# lower-board.net
KiCad netlist of a schematic drawn in EAGLE
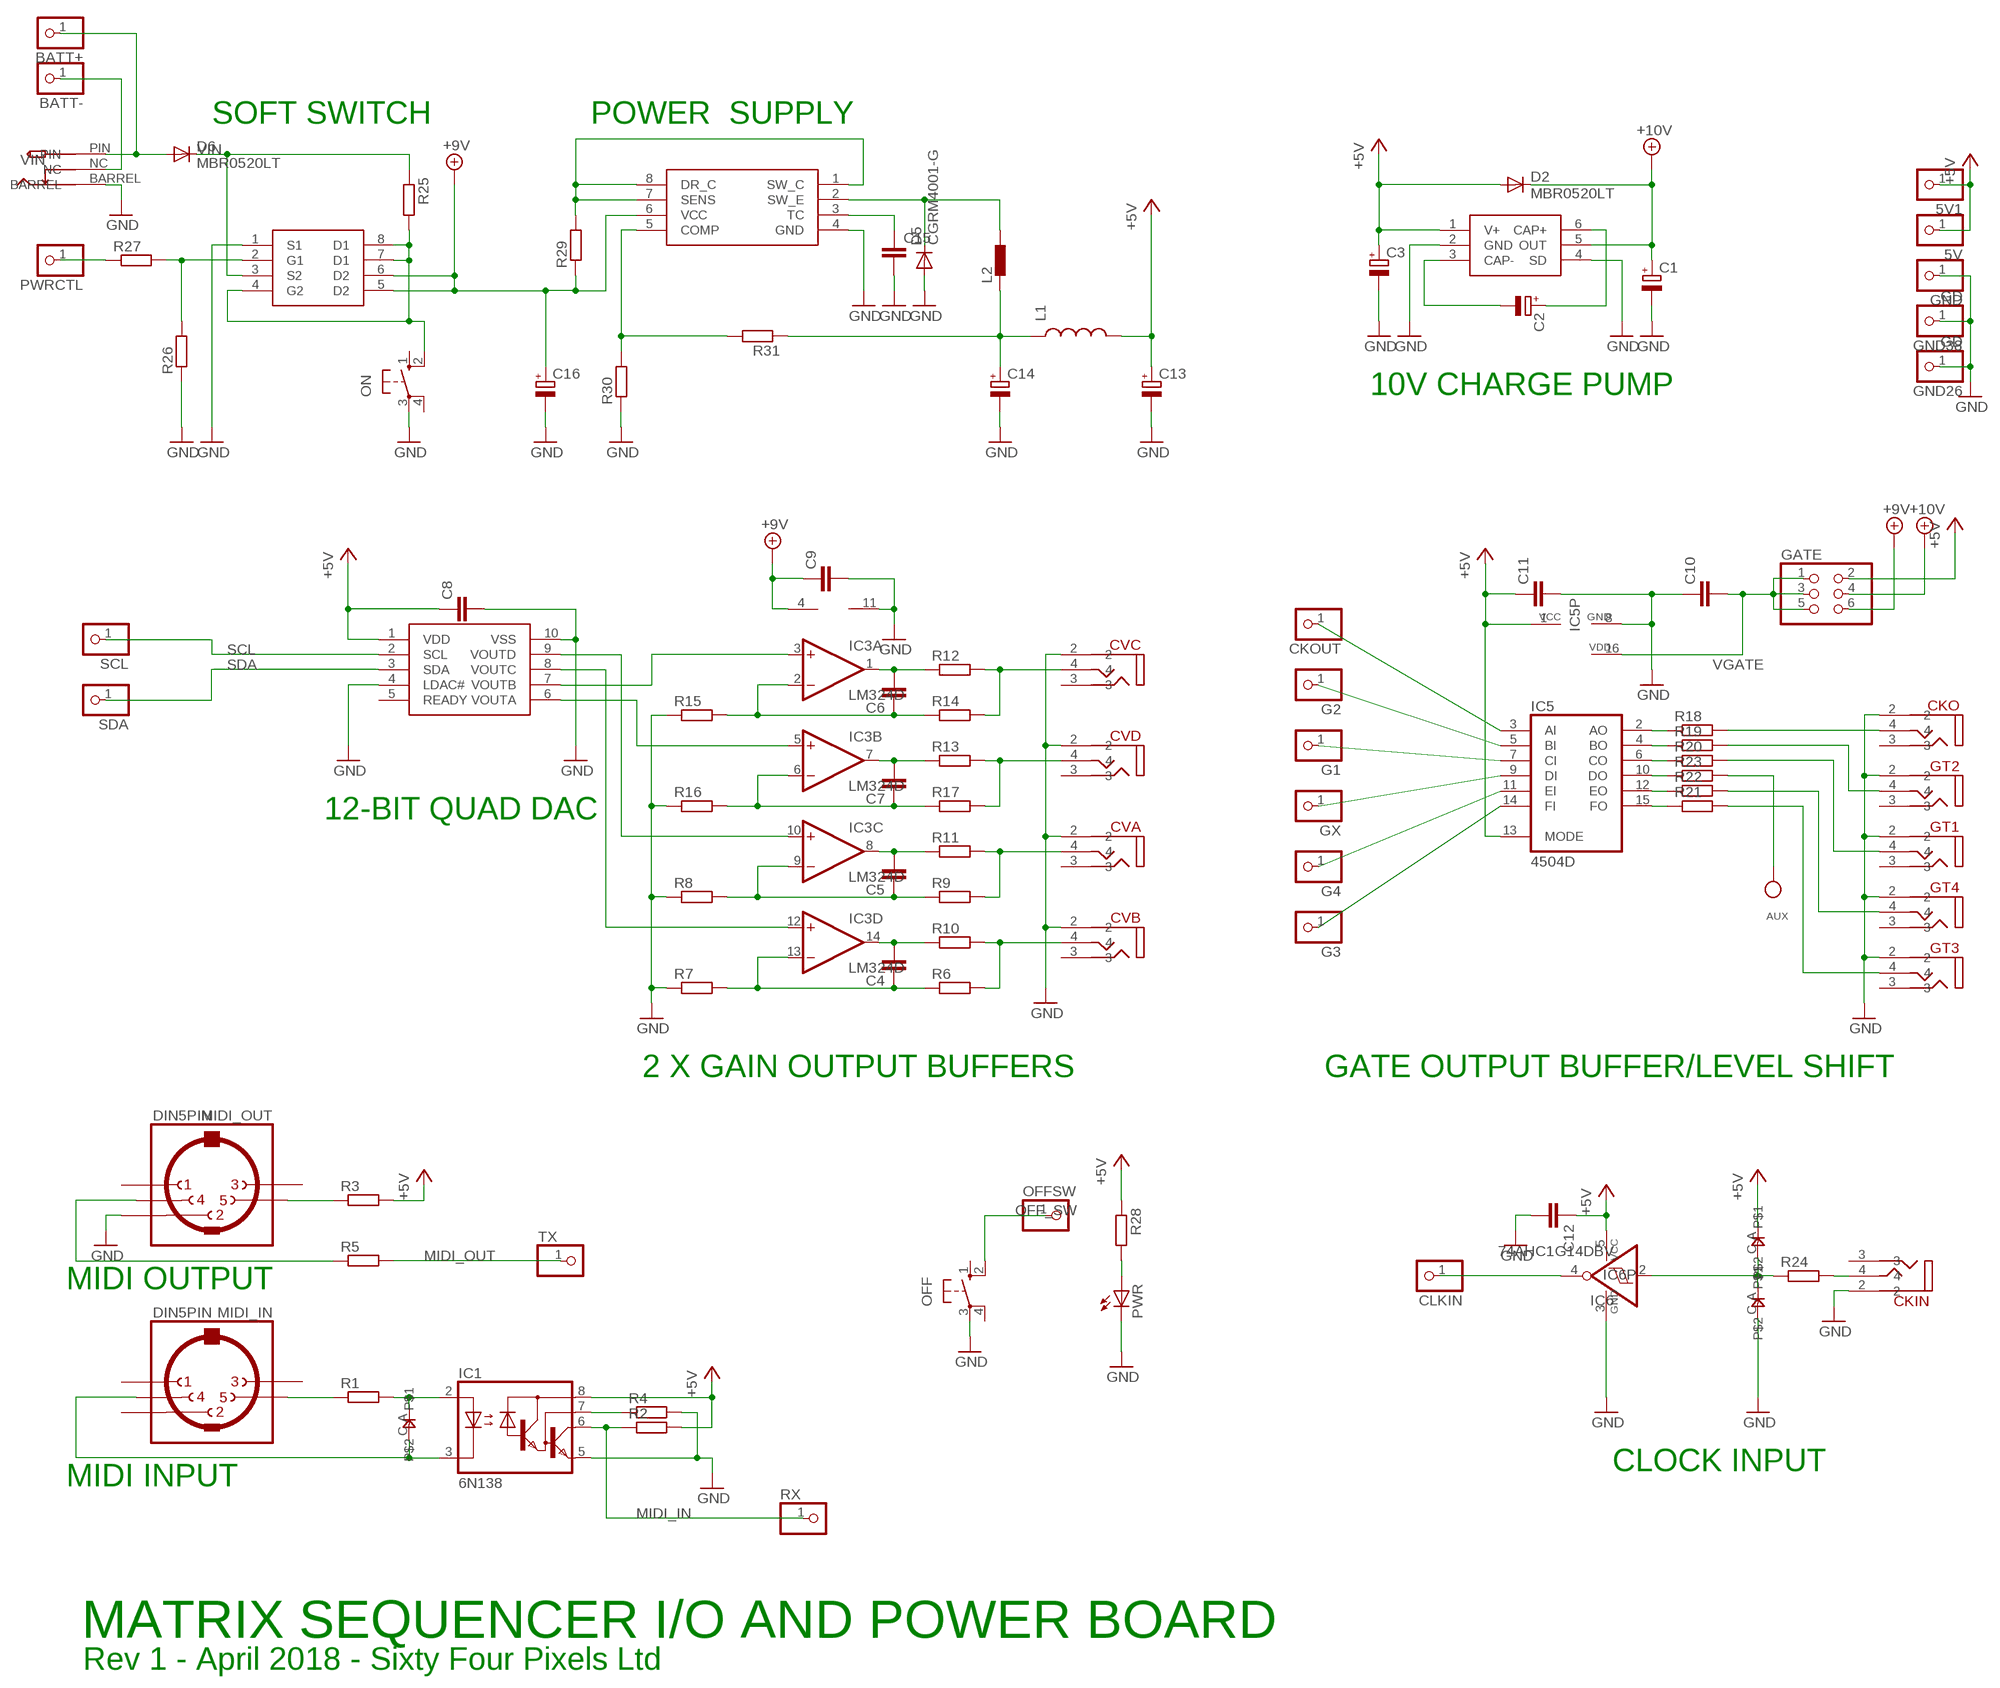
[diagram p0: schematic, sheet 1]

(export (version "E")
  (design (tool "Eeschema 10.0.6"))
  (components
    (comp (ref "5V")
      (value "PINHD-1X1")
      (footprint "eagle-import:1X01")
      (libsource (lib "eagle-import") (part "PINHD-1X1"))
    )
    (comp (ref "5V1")
      (value "PINHD-1X1")
      (footprint "eagle-import:1X01")
      (libsource (lib "eagle-import") (part "PINHD-1X1"))
    )
    (comp (ref "AUX")
      (value "TESTPOINTROUND2MM")
      (footprint "eagle-import:TESTPOINT_ROUND_2MM")
      (libsource (lib "eagle-import") (part "TESTPOINTROUND2MM"))
    )
    (comp (ref "BATT+")
      (value "PINHD-1X1")
      (footprint "eagle-import:1X01")
      (libsource (lib "eagle-import") (part "PINHD-1X1"))
    )
    (comp (ref "BATT-")
      (value "PINHD-1X1")
      (footprint "eagle-import:1X01")
      (libsource (lib "eagle-import") (part "PINHD-1X1"))
    )
    (comp (ref "C1")
      (value "CPOL-EUSMCA")
      (footprint "eagle-import:SMC_A")
      (libsource (lib "eagle-import") (part "CPOL-EUSMCA"))
    )
    (comp (ref "C2")
      (value "CPOL-EUSMCA")
      (footprint "eagle-import:SMC_A")
      (libsource (lib "eagle-import") (part "CPOL-EUSMCA"))
    )
    (comp (ref "C3")
      (value "CPOL-EUSMCA")
      (footprint "eagle-import:SMC_A")
      (libsource (lib "eagle-import") (part "CPOL-EUSMCA"))
    )
    (comp (ref "C4")
      (value "C-EUC0805")
      (footprint "eagle-import:C0805")
      (libsource (lib "eagle-import") (part "C-EUC0805"))
    )
    (comp (ref "C5")
      (value "C-EUC0805")
      (footprint "eagle-import:C0805")
      (libsource (lib "eagle-import") (part "C-EUC0805"))
    )
    (comp (ref "C6")
      (value "C-EUC0805")
      (footprint "eagle-import:C0805")
      (libsource (lib "eagle-import") (part "C-EUC0805"))
    )
    (comp (ref "C7")
      (value "C-EUC0805")
      (footprint "eagle-import:C0805")
      (libsource (lib "eagle-import") (part "C-EUC0805"))
    )
    (comp (ref "C8")
      (value "C-EUC0805")
      (footprint "eagle-import:C0805")
      (libsource (lib "eagle-import") (part "C-EUC0805"))
    )
    (comp (ref "C9")
      (value "C-EUC0805")
      (footprint "eagle-import:C0805")
      (libsource (lib "eagle-import") (part "C-EUC0805"))
    )
    (comp (ref "C10")
      (value "C-EUC0805")
      (footprint "eagle-import:C0805")
      (libsource (lib "eagle-import") (part "C-EUC0805"))
    )
    (comp (ref "C11")
      (value "C-EUC0805")
      (footprint "eagle-import:C0805")
      (libsource (lib "eagle-import") (part "C-EUC0805"))
    )
    (comp (ref "C12")
      (value "C-EUC0805")
      (footprint "eagle-import:C0805")
      (libsource (lib "eagle-import") (part "C-EUC0805"))
    )
    (comp (ref "C13")
      (value "CPOL-EUE2.5-7")
      (footprint "eagle-import:E2,5-7")
      (libsource (lib "eagle-import") (part "CPOL-EUE2.5-7"))
    )
    (comp (ref "C14")
      (value "CPOL-EUE2.5-7")
      (footprint "eagle-import:E2,5-7")
      (libsource (lib "eagle-import") (part "CPOL-EUE2.5-7"))
    )
    (comp (ref "C15")
      (value "C-EUC0805")
      (footprint "eagle-import:C0805")
      (libsource (lib "eagle-import") (part "C-EUC0805"))
    )
    (comp (ref "C16")
      (value "CPOL-EUE2.5-7")
      (footprint "eagle-import:E2,5-7")
      (libsource (lib "eagle-import") (part "CPOL-EUE2.5-7"))
    )
    (comp (ref "CKIN")
      (value "VERTICAL_3_5MM_SOCKET")
      (footprint "eagle-import:VERTICAL_3_5MM_SOCKET")
      (libsource (lib "eagle-import") (part "VERTICAL_3_5MM_SOCKET"))
    )
    (comp (ref "CKO")
      (value "VERTICAL_3_5MM_SOCKET")
      (footprint "eagle-import:VERTICAL_3_5MM_SOCKET")
      (libsource (lib "eagle-import") (part "VERTICAL_3_5MM_SOCKET"))
    )
    (comp (ref "CKOUT")
      (value "PINHD-1X1")
      (footprint "eagle-import:1X01")
      (libsource (lib "eagle-import") (part "PINHD-1X1"))
    )
    (comp (ref "CLKIN")
      (value "PINHD-1X1")
      (footprint "eagle-import:1X01")
      (libsource (lib "eagle-import") (part "PINHD-1X1"))
    )
    (comp (ref "CVA")
      (value "VERTICAL_3_5MM_SOCKET")
      (footprint "eagle-import:VERTICAL_3_5MM_SOCKET")
      (libsource (lib "eagle-import") (part "VERTICAL_3_5MM_SOCKET"))
    )
    (comp (ref "CVB")
      (value "VERTICAL_3_5MM_SOCKET")
      (footprint "eagle-import:VERTICAL_3_5MM_SOCKET")
      (libsource (lib "eagle-import") (part "VERTICAL_3_5MM_SOCKET"))
    )
    (comp (ref "CVC")
      (value "VERTICAL_3_5MM_SOCKET")
      (footprint "eagle-import:VERTICAL_3_5MM_SOCKET")
      (libsource (lib "eagle-import") (part "VERTICAL_3_5MM_SOCKET"))
    )
    (comp (ref "CVD")
      (value "VERTICAL_3_5MM_SOCKET")
      (footprint "eagle-import:VERTICAL_3_5MM_SOCKET")
      (libsource (lib "eagle-import") (part "VERTICAL_3_5MM_SOCKET"))
    )
    (comp (ref "D1")
      (value "0805DIODE")
      (footprint "eagle-import:0805DIODE")
      (libsource (lib "eagle-import") (part "0805DIODE"))
    )
    (comp (ref "D2")
      (value "MBR0520LT")
      (footprint "eagle-import:SOD123")
      (libsource (lib "eagle-import") (part "MBR0520LT"))
    )
    (comp (ref "D3")
      (value "0805DIODE")
      (footprint "eagle-import:0805DIODE")
      (libsource (lib "eagle-import") (part "0805DIODE"))
    )
    (comp (ref "D4")
      (value "0805DIODE")
      (footprint "eagle-import:0805DIODE")
      (libsource (lib "eagle-import") (part "0805DIODE"))
    )
    (comp (ref "D5")
      (value "CGRM4001-G")
      (footprint "eagle-import:SOD-123_MINI-SMA")
      (libsource (lib "eagle-import") (part "CGRM400-G1"))
    )
    (comp (ref "D6")
      (value "MBR0520LT")
      (footprint "eagle-import:SOD123")
      (libsource (lib "eagle-import") (part "MBR0520LT"))
    )
    (comp (ref "G1")
      (value "PINHD-1X1")
      (footprint "eagle-import:1X01")
      (libsource (lib "eagle-import") (part "PINHD-1X1"))
    )
    (comp (ref "G2")
      (value "PINHD-1X1")
      (footprint "eagle-import:1X01")
      (libsource (lib "eagle-import") (part "PINHD-1X1"))
    )
    (comp (ref "G3")
      (value "PINHD-1X1")
      (footprint "eagle-import:1X01")
      (libsource (lib "eagle-import") (part "PINHD-1X1"))
    )
    (comp (ref "G4")
      (value "PINHD-1X1")
      (footprint "eagle-import:1X01")
      (libsource (lib "eagle-import") (part "PINHD-1X1"))
    )
    (comp (ref "GATE")
      (value "PINHD-2X3")
      (footprint "eagle-import:2X03")
      (libsource (lib "eagle-import") (part "PINHD-2X3"))
    )
    (comp (ref "GND")
      (value "PINHD-1X1")
      (footprint "eagle-import:1X01")
      (libsource (lib "eagle-import") (part "PINHD-1X1"))
    )
    (comp (ref "GND26")
      (value "GD")
      (footprint "eagle-import:1X01")
      (libsource (lib "eagle-import") (part "PINHD-1X1"))
    )
    (comp (ref "GND38")
      (value "GD")
      (footprint "eagle-import:1X01")
      (libsource (lib "eagle-import") (part "PINHD-1X1"))
    )
    (comp (ref "GT1")
      (value "VERTICAL_3_5MM_SOCKET")
      (footprint "eagle-import:VERTICAL_3_5MM_SOCKET")
      (libsource (lib "eagle-import") (part "VERTICAL_3_5MM_SOCKET"))
    )
    (comp (ref "GT2")
      (value "VERTICAL_3_5MM_SOCKET")
      (footprint "eagle-import:VERTICAL_3_5MM_SOCKET")
      (libsource (lib "eagle-import") (part "VERTICAL_3_5MM_SOCKET"))
    )
    (comp (ref "GT3")
      (value "VERTICAL_3_5MM_SOCKET")
      (footprint "eagle-import:VERTICAL_3_5MM_SOCKET")
      (libsource (lib "eagle-import") (part "VERTICAL_3_5MM_SOCKET"))
    )
    (comp (ref "GT4")
      (value "VERTICAL_3_5MM_SOCKET")
      (footprint "eagle-import:VERTICAL_3_5MM_SOCKET")
      (libsource (lib "eagle-import") (part "VERTICAL_3_5MM_SOCKET"))
    )
    (comp (ref "GX")
      (value "PINHD-1X1")
      (footprint "eagle-import:1X01")
      (libsource (lib "eagle-import") (part "PINHD-1X1"))
    )
    (comp (ref "IC1")
      (value "6N138")
      (footprint "eagle-import:DIL08")
      (fields (field (name "MF") "VISHAY/TELEFUNKEN"))
      (libsource (lib "eagle-import") (part "6N138"))
    )
    (comp (ref "IC2")
      (value "LM27675M5_CHARGEPUMP")
      (footprint "eagle-import:SOT23-6")
      (libsource (lib "eagle-import") (part "LM27675M5_CHARGEPUMP"))
    )
    (comp (ref "IC3")
      (value "LM324D")
      (footprint "eagle-import:SO14")
      (libsource (lib "eagle-import") (part "LM324D"))
    )
    (comp (ref "IC4")
      (value "MCP4728_QUAD_DAC")
      (footprint "eagle-import:MSOP10")
      (libsource (lib "eagle-import") (part "MCP4728_QUAD_DAC"))
    )
    (comp (ref "IC5")
      (value "4504D")
      (footprint "eagle-import:SO16")
      (libsource (lib "eagle-import") (part "4504D"))
    )
    (comp (ref "IC6")
      (value "74AHC1G14DBV")
      (footprint "eagle-import:SOT23-5")
      (libsource (lib "eagle-import") (part "741G14DBVAHC"))
    )
    (comp (ref "IC7")
      (value "FDS8958B")
      (footprint "eagle-import:SOIC8")
      (libsource (lib "eagle-import") (part "FDS8958B"))
    )
    (comp (ref "IC8")
      (value "SP34063A_BOOST_REG")
      (footprint "eagle-import:SOIC8")
      (libsource (lib "eagle-import") (part "SP34063A_BOOST_REG"))
    )
    (comp (ref "L1")
      (value "INDUCTOR1210")
      (footprint "eagle-import:1210")
      (libsource (lib "eagle-import") (part "INDUCTOR1210"))
    )
    (comp (ref "L2")
      (value "DR1030")
      (footprint "eagle-import:DR1030")
      (libsource (lib "eagle-import") (part "DR1030"))
    )
    (comp (ref "MIDI_IN")
      (value "DIN5PIN")
      (footprint "eagle-import:EDGEDIN")
      (libsource (lib "eagle-import") (part "DIN5PIN"))
    )
    (comp (ref "MIDI_OUT")
      (value "DIN5PIN")
      (footprint "eagle-import:EDGEDIN")
      (libsource (lib "eagle-import") (part "DIN5PIN"))
    )
    (comp (ref "OFF")
      (value "10-XX")
      (footprint "eagle-import:B3F-10XX")
      (fields (field (name "MPN") "B3F-1000"))
      (libsource (lib "eagle-import") (part "10-XX"))
    )
    (comp (ref "OFFSW")
      (value "PINHD-1X1")
      (footprint "eagle-import:1X01")
      (libsource (lib "eagle-import") (part "PINHD-1X1"))
    )
    (comp (ref "ON")
      (value "10-XX")
      (footprint "eagle-import:B3F-10XX")
      (fields (field (name "MPN") "B3F-1000"))
      (libsource (lib "eagle-import") (part "10-XX"))
    )
    (comp (ref "PWR")
      (value "LED3MM")
      (footprint "eagle-import:LED3MM")
      (libsource (lib "eagle-import") (part "LED3MM"))
    )
    (comp (ref "PWRCTL")
      (value "PINHD-1X1")
      (footprint "eagle-import:1X01")
      (libsource (lib "eagle-import") (part "PINHD-1X1"))
    )
    (comp (ref "R1")
      (value "R-EU_R0805")
      (footprint "eagle-import:R0805")
      (libsource (lib "eagle-import") (part "R-EU_R0805"))
    )
    (comp (ref "R2")
      (value "R-EU_R0805")
      (footprint "eagle-import:R0805")
      (libsource (lib "eagle-import") (part "R-EU_R0805"))
    )
    (comp (ref "R3")
      (value "R-EU_R0805")
      (footprint "eagle-import:R0805")
      (libsource (lib "eagle-import") (part "R-EU_R0805"))
    )
    (comp (ref "R4")
      (value "R-EU_R0805")
      (footprint "eagle-import:R0805")
      (libsource (lib "eagle-import") (part "R-EU_R0805"))
    )
    (comp (ref "R5")
      (value "R-EU_R0805")
      (footprint "eagle-import:R0805")
      (libsource (lib "eagle-import") (part "R-EU_R0805"))
    )
    (comp (ref "R6")
      (value "R-EU_R0805")
      (footprint "eagle-import:R0805")
      (libsource (lib "eagle-import") (part "R-EU_R0805"))
    )
    (comp (ref "R7")
      (value "R-EU_R0805")
      (footprint "eagle-import:R0805")
      (libsource (lib "eagle-import") (part "R-EU_R0805"))
    )
    (comp (ref "R8")
      (value "R-EU_R0805")
      (footprint "eagle-import:R0805")
      (libsource (lib "eagle-import") (part "R-EU_R0805"))
    )
    (comp (ref "R9")
      (value "R-EU_R0805")
      (footprint "eagle-import:R0805")
      (libsource (lib "eagle-import") (part "R-EU_R0805"))
    )
    (comp (ref "R10")
      (value "R-EU_R0805")
      (footprint "eagle-import:R0805")
      (libsource (lib "eagle-import") (part "R-EU_R0805"))
    )
    (comp (ref "R11")
      (value "R-EU_R0805")
      (footprint "eagle-import:R0805")
      (libsource (lib "eagle-import") (part "R-EU_R0805"))
    )
    (comp (ref "R12")
      (value "R-EU_R0805")
      (footprint "eagle-import:R0805")
      (libsource (lib "eagle-import") (part "R-EU_R0805"))
    )
    (comp (ref "R13")
      (value "R-EU_R0805")
      (footprint "eagle-import:R0805")
      (libsource (lib "eagle-import") (part "R-EU_R0805"))
    )
    (comp (ref "R14")
      (value "R-EU_R0805")
      (footprint "eagle-import:R0805")
      (libsource (lib "eagle-import") (part "R-EU_R0805"))
    )
    (comp (ref "R15")
      (value "R-EU_R0805")
      (footprint "eagle-import:R0805")
      (libsource (lib "eagle-import") (part "R-EU_R0805"))
    )
    (comp (ref "R16")
      (value "R-EU_R0805")
      (footprint "eagle-import:R0805")
      (libsource (lib "eagle-import") (part "R-EU_R0805"))
    )
    (comp (ref "R17")
      (value "R-EU_R0805")
      (footprint "eagle-import:R0805")
      (libsource (lib "eagle-import") (part "R-EU_R0805"))
    )
    (comp (ref "R18")
      (value "R-EU_R0805")
      (footprint "eagle-import:R0805")
      (libsource (lib "eagle-import") (part "R-EU_R0805"))
    )
    (comp (ref "R19")
      (value "R-EU_R0805")
      (footprint "eagle-import:R0805")
      (libsource (lib "eagle-import") (part "R-EU_R0805"))
    )
    (comp (ref "R20")
      (value "R-EU_R0805")
      (footprint "eagle-import:R0805")
      (libsource (lib "eagle-import") (part "R-EU_R0805"))
    )
    (comp (ref "R21")
      (value "R-EU_R0805")
      (footprint "eagle-import:R0805")
      (libsource (lib "eagle-import") (part "R-EU_R0805"))
    )
    (comp (ref "R22")
      (value "R-EU_R0805")
      (footprint "eagle-import:R0805")
      (libsource (lib "eagle-import") (part "R-EU_R0805"))
    )
    (comp (ref "R23")
      (value "R-EU_R0805")
      (footprint "eagle-import:R0805")
      (libsource (lib "eagle-import") (part "R-EU_R0805"))
    )
    (comp (ref "R24")
      (value "R-EU_R0805")
      (footprint "eagle-import:R0805")
      (libsource (lib "eagle-import") (part "R-EU_R0805"))
    )
    (comp (ref "R25")
      (value "R-EU_R0805")
      (footprint "eagle-import:R0805")
      (libsource (lib "eagle-import") (part "R-EU_R0805"))
    )
    (comp (ref "R26")
      (value "R-EU_R0805")
      (footprint "eagle-import:R0805")
      (libsource (lib "eagle-import") (part "R-EU_R0805"))
    )
    (comp (ref "R27")
      (value "R-EU_R0805")
      (footprint "eagle-import:R0805")
      (libsource (lib "eagle-import") (part "R-EU_R0805"))
    )
    (comp (ref "R28")
      (value "R-EU_R0805")
      (footprint "eagle-import:R0805")
      (libsource (lib "eagle-import") (part "R-EU_R0805"))
    )
    (comp (ref "R29")
      (value "R-EU_R0805")
      (footprint "eagle-import:R0805")
      (libsource (lib "eagle-import") (part "R-EU_R0805"))
    )
    (comp (ref "R30")
      (value "R-EU_R0805")
      (footprint "eagle-import:R0805")
      (libsource (lib "eagle-import") (part "R-EU_R0805"))
    )
    (comp (ref "R31")
      (value "R-EU_R0805")
      (footprint "eagle-import:R0805")
      (libsource (lib "eagle-import") (part "R-EU_R0805"))
    )
    (comp (ref "RX")
      (value "PINHD-1X1")
      (footprint "eagle-import:1X01")
      (libsource (lib "eagle-import") (part "PINHD-1X1"))
    )
    (comp (ref "SCL")
      (value "PINHD-1X1")
      (footprint "eagle-import:1X01")
      (libsource (lib "eagle-import") (part "PINHD-1X1"))
    )
    (comp (ref "SDA")
      (value "PINHD-1X1")
      (footprint "eagle-import:1X01")
      (libsource (lib "eagle-import") (part "PINHD-1X1"))
    )
    (comp (ref "TX")
      (value "PINHD-1X1")
      (footprint "eagle-import:1X01")
      (libsource (lib "eagle-import") (part "PINHD-1X1"))
    )
    (comp (ref "U$1")
      (value "PWR_SOCKET_2_1MM")
      (footprint "eagle-import:PWR_SOCKET_2_1MM")
      (libsource (lib "eagle-import") (part "PWR_SOCKET_2_1MM"))
    )
  )
  (nets
    (net (code "1") (name "+5V") (class "Default")
      (node (ref "5V") (pin "1") (pinfunction "1_1") (pintype "passive"))
      (node (ref "5V1") (pin "1") (pinfunction "1_1") (pintype "passive"))
      (node (ref "C11") (pin "1") (pinfunction "1_1") (pintype "passive"))
      (node (ref "C12") (pin "1") (pinfunction "1_1") (pintype "passive"))
      (node (ref "C13") (pin "+") (pinfunction "+_+") (pintype "passive"))
      (node (ref "C3") (pin "+") (pinfunction "+_+") (pintype "passive"))
      (node (ref "C8") (pin "1") (pinfunction "1_1") (pintype "passive"))
      (node (ref "D2") (pin "A") (pinfunction "A_A") (pintype "passive"))
      (node (ref "D3") (pin "A") (pinfunction "P$2_A") (pintype "bidirectional"))
      (node (ref "GATE") (pin "2") (pinfunction "2_2") (pintype "passive"))
      (node (ref "IC1") (pin "8") (pinfunction "VCC_8") (pintype "passive"))
      (node (ref "IC2") (pin "1") (pinfunction "V+_1") (pintype "bidirectional"))
      (node (ref "IC4") (pin "1") (pinfunction "VDD_1") (pintype "power_in"))
      (node (ref "IC5") (pin "1") (pinfunction "VCC_1") (pintype "power_in"))
      (node (ref "IC5") (pin "13") (pinfunction "MODE_13") (pintype "input"))
      (node (ref "IC6") (pin "5") (pinfunction "VCC_5") (pintype "power_in"))
      (node (ref "L1") (pin "2") (pinfunction "2_2") (pintype "passive"))
      (node (ref "R2") (pin "2") (pinfunction "2_2") (pintype "passive"))
      (node (ref "R28") (pin "1") (pinfunction "1_1") (pintype "passive"))
      (node (ref "R3") (pin "2") (pinfunction "2_2") (pintype "passive"))
    )
    (net (code "2") (name "+9V") (class "Default")
      (node (ref "C16") (pin "+") (pinfunction "+_+") (pintype "passive"))
      (node (ref "C9") (pin "1") (pinfunction "1_1") (pintype "passive"))
      (node (ref "GATE") (pin "6") (pinfunction "6_6") (pintype "passive"))
      (node (ref "IC3") (pin "4") (pinfunction "V+_4") (pintype "power_in"))
      (node (ref "IC7") (pin "5") (pinfunction "D2_5") (pintype "bidirectional"))
      (node (ref "IC7") (pin "6") (pinfunction "D2_6") (pintype "bidirectional"))
      (node (ref "IC8") (pin "6") (pinfunction "VCC_6") (pintype "bidirectional"))
      (node (ref "R29") (pin "1") (pinfunction "1_1") (pintype "passive"))
    )
    (net (code "3") (name "+10V") (class "Default")
      (node (ref "C1") (pin "+") (pinfunction "+_+") (pintype "passive"))
      (node (ref "D2") (pin "C") (pinfunction "C_C") (pintype "passive"))
      (node (ref "GATE") (pin "4") (pinfunction "4_4") (pintype "passive"))
      (node (ref "IC2") (pin "5") (pinfunction "OUT_5") (pintype "bidirectional"))
    )
    (net (code "4") (name "/MIDI_IN") (class "Default")
      (node (ref "IC1") (pin "6") (pinfunction "VO_6") (pintype "passive"))
      (node (ref "R2") (pin "1") (pinfunction "1_1") (pintype "passive"))
      (node (ref "RX") (pin "1") (pinfunction "1_1") (pintype "passive"))
    )
    (net (code "5") (name "/MIDI_OUT") (class "Default")
      (node (ref "R5") (pin "2") (pinfunction "2_2") (pintype "passive"))
      (node (ref "TX") (pin "1") (pinfunction "1_1") (pintype "passive"))
    )
    (net (code "6") (name "/OFF_SW") (class "Default")
      (node (ref "OFF") (pin "2") (pinfunction "S1_2") (pintype "passive"))
      (node (ref "OFFSW") (pin "1") (pinfunction "1_1") (pintype "passive"))
    )
    (net (code "7") (name "/SCL") (class "Default")
      (node (ref "IC4") (pin "2") (pinfunction "SCL_2") (pintype "bidirectional"))
      (node (ref "SCL") (pin "1") (pinfunction "1_1") (pintype "passive"))
    )
    (net (code "8") (name "/SDA") (class "Default")
      (node (ref "IC4") (pin "3") (pinfunction "SDA_3") (pintype "bidirectional"))
      (node (ref "SDA") (pin "1") (pinfunction "1_1") (pintype "passive"))
    )
    (net (code "9") (name "/VGATE") (class "Default")
      (node (ref "C10") (pin "2") (pinfunction "2_2") (pintype "passive"))
      (node (ref "GATE") (pin "1") (pinfunction "1_1") (pintype "passive"))
      (node (ref "GATE") (pin "3") (pinfunction "3_3") (pintype "passive"))
      (node (ref "GATE") (pin "5") (pinfunction "5_5") (pintype "passive"))
      (node (ref "IC5") (pin "16") (pinfunction "VDD_16") (pintype "power_in"))
    )
    (net (code "10") (name "/VIN") (class "Default")
      (node (ref "D6") (pin "C") (pinfunction "C_C") (pintype "passive"))
      (node (ref "IC7") (pin "3") (pinfunction "S2_3") (pintype "bidirectional"))
      (node (ref "R25") (pin "1") (pinfunction "1_1") (pintype "passive"))
    )
    (net (code "11") (name "GND") (class "Default")
      (node (ref "C1") (pin "-") (pinfunction "-_-") (pintype "passive"))
      (node (ref "C10") (pin "1") (pinfunction "1_1") (pintype "passive"))
      (node (ref "C11") (pin "2") (pinfunction "2_2") (pintype "passive"))
      (node (ref "C12") (pin "2") (pinfunction "2_2") (pintype "passive"))
      (node (ref "C13") (pin "-") (pinfunction "-_-") (pintype "passive"))
      (node (ref "C14") (pin "-") (pinfunction "-_-") (pintype "passive"))
      (node (ref "C15") (pin "2") (pinfunction "2_2") (pintype "passive"))
      (node (ref "C16") (pin "-") (pinfunction "-_-") (pintype "passive"))
      (node (ref "C3") (pin "-") (pinfunction "-_-") (pintype "passive"))
      (node (ref "C8") (pin "2") (pinfunction "2_2") (pintype "passive"))
      (node (ref "C9") (pin "2") (pinfunction "2_2") (pintype "passive"))
      (node (ref "CKIN") (pin "2") (pinfunction "2_2") (pintype "bidirectional"))
      (node (ref "CKO") (pin "2") (pinfunction "2_2") (pintype "bidirectional"))
      (node (ref "CVA") (pin "2") (pinfunction "2_2") (pintype "bidirectional"))
      (node (ref "CVB") (pin "2") (pinfunction "2_2") (pintype "bidirectional"))
      (node (ref "CVC") (pin "2") (pinfunction "2_2") (pintype "bidirectional"))
      (node (ref "CVD") (pin "2") (pinfunction "2_2") (pintype "bidirectional"))
      (node (ref "D4") (pin "C") (pinfunction "P$1_C") (pintype "bidirectional"))
      (node (ref "D5") (pin "A") (pinfunction "A_A") (pintype "passive"))
      (node (ref "GND") (pin "1") (pinfunction "1_1") (pintype "passive"))
      (node (ref "GND26") (pin "1") (pinfunction "1_1") (pintype "passive"))
      (node (ref "GND38") (pin "1") (pinfunction "1_1") (pintype "passive"))
      (node (ref "GT1") (pin "2") (pinfunction "2_2") (pintype "bidirectional"))
      (node (ref "GT2") (pin "2") (pinfunction "2_2") (pintype "bidirectional"))
      (node (ref "GT3") (pin "2") (pinfunction "2_2") (pintype "bidirectional"))
      (node (ref "GT4") (pin "2") (pinfunction "2_2") (pintype "bidirectional"))
      (node (ref "IC1") (pin "5") (pinfunction "GND_5") (pintype "passive"))
      (node (ref "IC2") (pin "2") (pinfunction "GND_2") (pintype "bidirectional"))
      (node (ref "IC2") (pin "4") (pinfunction "SD_4") (pintype "bidirectional"))
      (node (ref "IC3") (pin "11") (pinfunction "V-_11") (pintype "power_in"))
      (node (ref "IC4") (pin "10") (pinfunction "VSS_10") (pintype "power_in"))
      (node (ref "IC4") (pin "4") (pinfunction "LDAC#_4") (pintype "bidirectional"))
      (node (ref "IC5") (pin "8") (pinfunction "GND_8") (pintype "power_in"))
      (node (ref "IC6") (pin "3") (pinfunction "GND_3") (pintype "power_in"))
      (node (ref "IC7") (pin "1") (pinfunction "S1_1") (pintype "bidirectional"))
      (node (ref "IC8") (pin "4") (pinfunction "GND_4") (pintype "bidirectional"))
      (node (ref "MIDI_OUT") (pin "2") (pinfunction "2_2") (pintype "passive"))
      (node (ref "OFF") (pin "3") (pinfunction "P_3") (pintype "passive"))
      (node (ref "ON") (pin "3") (pinfunction "P_3") (pintype "passive"))
      (node (ref "PWR") (pin "K") (pinfunction "C_K") (pintype "passive"))
      (node (ref "R15") (pin "1") (pinfunction "1_1") (pintype "passive"))
      (node (ref "R16") (pin "1") (pinfunction "1_1") (pintype "passive"))
      (node (ref "R26") (pin "1") (pinfunction "1_1") (pintype "passive"))
      (node (ref "R30") (pin "1") (pinfunction "1_1") (pintype "passive"))
      (node (ref "R4") (pin "2") (pinfunction "2_2") (pintype "passive"))
      (node (ref "R7") (pin "1") (pinfunction "1_1") (pintype "passive"))
      (node (ref "R8") (pin "1") (pinfunction "1_1") (pintype "passive"))
      (node (ref "U$1") (pin "BARREL") (pinfunction "BARREL_BARREL") (pintype "bidirectional"))
    )
    (net (code "12") (name "Net-(AUX-PadP$1)") (class "Default")
      (node (ref "AUX") (pin "P$1") (pinfunction "P$1_P$1") (pintype "bidirectional"))
      (node (ref "R23") (pin "2") (pinfunction "2_2") (pintype "passive"))
    )
    (net (code "13") (name "Net-(BATT+-Pad1)") (class "Default")
      (node (ref "BATT+") (pin "1") (pinfunction "1_1") (pintype "passive"))
      (node (ref "D6") (pin "A") (pinfunction "A_A") (pintype "passive"))
      (node (ref "U$1") (pin "PIN") (pinfunction "PIN_PIN") (pintype "bidirectional"))
    )
    (net (code "14") (name "Net-(BATT--Pad1)") (class "Default")
      (node (ref "BATT-") (pin "1") (pinfunction "1_1") (pintype "passive"))
      (node (ref "U$1") (pin "NC") (pinfunction "NC_NC") (pintype "bidirectional"))
    )
    (net (code "15") (name "Net-(C14-Pad+)") (class "Default")
      (node (ref "C14") (pin "+") (pinfunction "+_+") (pintype "passive"))
      (node (ref "L1") (pin "1") (pinfunction "1_1") (pintype "passive"))
      (node (ref "L2") (pin "1") (pinfunction "1_1") (pintype "passive"))
      (node (ref "R31") (pin "1") (pinfunction "1_1") (pintype "passive"))
    )
    (net (code "16") (name "Net-(CKIN-Pad4)") (class "Default")
      (node (ref "CKIN") (pin "4") (pinfunction "4_4") (pintype "bidirectional"))
      (node (ref "R24") (pin "2") (pinfunction "2_2") (pintype "passive"))
    )
    (net (code "17") (name "Net-(CKO-Pad4)") (class "Default")
      (node (ref "CKO") (pin "4") (pinfunction "4_4") (pintype "bidirectional"))
      (node (ref "R18") (pin "2") (pinfunction "2_2") (pintype "passive"))
    )
    (net (code "18") (name "Net-(CVA-Pad4)") (class "Default")
      (node (ref "CVA") (pin "4") (pinfunction "4_4") (pintype "bidirectional"))
      (node (ref "R11") (pin "2") (pinfunction "2_2") (pintype "passive"))
      (node (ref "R9") (pin "2") (pinfunction "2_2") (pintype "passive"))
    )
    (net (code "19") (name "Net-(CVB-Pad4)") (class "Default")
      (node (ref "CVB") (pin "4") (pinfunction "4_4") (pintype "bidirectional"))
      (node (ref "R10") (pin "2") (pinfunction "2_2") (pintype "passive"))
      (node (ref "R6") (pin "2") (pinfunction "2_2") (pintype "passive"))
    )
    (net (code "20") (name "Net-(CVC-Pad4)") (class "Default")
      (node (ref "CVC") (pin "4") (pinfunction "4_4") (pintype "bidirectional"))
      (node (ref "R12") (pin "2") (pinfunction "2_2") (pintype "passive"))
      (node (ref "R14") (pin "2") (pinfunction "2_2") (pintype "passive"))
    )
    (net (code "21") (name "Net-(CVD-Pad4)") (class "Default")
      (node (ref "CVD") (pin "4") (pinfunction "4_4") (pintype "bidirectional"))
      (node (ref "R13") (pin "2") (pinfunction "2_2") (pintype "passive"))
      (node (ref "R17") (pin "2") (pinfunction "2_2") (pintype "passive"))
    )
    (net (code "22") (name "Net-(D1-P$1)") (class "Default")
      (node (ref "D1") (pin "C") (pinfunction "P$1_C") (pintype "bidirectional"))
      (node (ref "IC1") (pin "3") (pinfunction "C_3") (pintype "passive"))
      (node (ref "MIDI_IN") (pin "4") (pinfunction "4_4") (pintype "passive"))
    )
    (net (code "23") (name "Net-(D1-P$2)") (class "Default")
      (node (ref "D1") (pin "A") (pinfunction "P$2_A") (pintype "bidirectional"))
      (node (ref "IC1") (pin "2") (pinfunction "A_2") (pintype "passive"))
      (node (ref "R1") (pin "2") (pinfunction "2_2") (pintype "passive"))
    )
    (net (code "24") (name "Net-(D3-P$1)") (class "Default")
      (node (ref "D3") (pin "C") (pinfunction "P$1_C") (pintype "bidirectional"))
      (node (ref "D4") (pin "A") (pinfunction "P$2_A") (pintype "bidirectional"))
      (node (ref "IC6") (pin "2") (pinfunction "I_2") (pintype "input"))
      (node (ref "R24") (pin "1") (pinfunction "1_1") (pintype "passive"))
    )
    (net (code "25") (name "Net-(GT1-Pad4)") (class "Default")
      (node (ref "GT1") (pin "4") (pinfunction "4_4") (pintype "bidirectional"))
      (node (ref "R20") (pin "2") (pinfunction "2_2") (pintype "passive"))
    )
    (net (code "26") (name "Net-(GT2-Pad4)") (class "Default")
      (node (ref "GT2") (pin "4") (pinfunction "4_4") (pintype "bidirectional"))
      (node (ref "R19") (pin "2") (pinfunction "2_2") (pintype "passive"))
    )
    (net (code "27") (name "Net-(GT3-Pad4)") (class "Default")
      (node (ref "GT3") (pin "4") (pinfunction "4_4") (pintype "bidirectional"))
      (node (ref "R21") (pin "2") (pinfunction "2_2") (pintype "passive"))
    )
    (net (code "28") (name "Net-(GT4-Pad4)") (class "Default")
      (node (ref "GT4") (pin "4") (pinfunction "4_4") (pintype "bidirectional"))
      (node (ref "R22") (pin "2") (pinfunction "2_2") (pintype "passive"))
    )
    (net (code "29") (name "Net-(IC1-VB)") (class "Default")
      (node (ref "IC1") (pin "7") (pinfunction "VB_7") (pintype "passive"))
      (node (ref "R4") (pin "1") (pinfunction "1_1") (pintype "passive"))
    )
    (net (code "30") (name "Net-(IC2-CAP+)") (class "Default")
      (node (ref "C2") (pin "+") (pinfunction "+_+") (pintype "passive"))
      (node (ref "IC2") (pin "6") (pinfunction "CAP+_6") (pintype "bidirectional"))
    )
    (net (code "31") (name "Net-(IC2-CAP-)") (class "Default")
      (node (ref "C2") (pin "-") (pinfunction "-_-") (pintype "passive"))
      (node (ref "IC2") (pin "3") (pinfunction "CAP-_3") (pintype "bidirectional"))
    )
    (net (code "32") (name "Net-(IC3A-+IN)") (class "Default")
      (node (ref "IC3") (pin "3") (pinfunction "+IN_3") (pintype "input"))
      (node (ref "IC4") (pin "7") (pinfunction "VOUTB_7") (pintype "bidirectional"))
    )
    (net (code "33") (name "Net-(IC3A--IN)") (class "Default")
      (node (ref "C6") (pin "1") (pinfunction "1_1") (pintype "passive"))
      (node (ref "IC3") (pin "2") (pinfunction "-IN_2") (pintype "input"))
      (node (ref "R14") (pin "1") (pinfunction "1_1") (pintype "passive"))
      (node (ref "R15") (pin "2") (pinfunction "2_2") (pintype "passive"))
    )
    (net (code "34") (name "Net-(IC3A-OUT)") (class "Default")
      (node (ref "C6") (pin "2") (pinfunction "2_2") (pintype "passive"))
      (node (ref "IC3") (pin "1") (pinfunction "OUT_1") (pintype "output"))
      (node (ref "R12") (pin "1") (pinfunction "1_1") (pintype "passive"))
    )
    (net (code "35") (name "Net-(IC3B-+IN)") (class "Default")
      (node (ref "IC3") (pin "5") (pinfunction "+IN_5") (pintype "input"))
      (node (ref "IC4") (pin "6") (pinfunction "VOUTA_6") (pintype "bidirectional"))
    )
    (net (code "36") (name "Net-(IC3B--IN)") (class "Default")
      (node (ref "C7") (pin "1") (pinfunction "1_1") (pintype "passive"))
      (node (ref "IC3") (pin "6") (pinfunction "-IN_6") (pintype "input"))
      (node (ref "R16") (pin "2") (pinfunction "2_2") (pintype "passive"))
      (node (ref "R17") (pin "1") (pinfunction "1_1") (pintype "passive"))
    )
    (net (code "37") (name "Net-(IC3B-OUT)") (class "Default")
      (node (ref "C7") (pin "2") (pinfunction "2_2") (pintype "passive"))
      (node (ref "IC3") (pin "7") (pinfunction "OUT_7") (pintype "output"))
      (node (ref "R13") (pin "1") (pinfunction "1_1") (pintype "passive"))
    )
    (net (code "38") (name "Net-(IC3C-+IN)") (class "Default")
      (node (ref "IC3") (pin "10") (pinfunction "+IN_10") (pintype "input"))
      (node (ref "IC4") (pin "9") (pinfunction "VOUTD_9") (pintype "bidirectional"))
    )
    (net (code "39") (name "Net-(IC3C--IN)") (class "Default")
      (node (ref "C5") (pin "1") (pinfunction "1_1") (pintype "passive"))
      (node (ref "IC3") (pin "9") (pinfunction "-IN_9") (pintype "input"))
      (node (ref "R8") (pin "2") (pinfunction "2_2") (pintype "passive"))
      (node (ref "R9") (pin "1") (pinfunction "1_1") (pintype "passive"))
    )
    (net (code "40") (name "Net-(IC3C-OUT)") (class "Default")
      (node (ref "C5") (pin "2") (pinfunction "2_2") (pintype "passive"))
      (node (ref "IC3") (pin "8") (pinfunction "OUT_8") (pintype "output"))
      (node (ref "R11") (pin "1") (pinfunction "1_1") (pintype "passive"))
    )
    (net (code "41") (name "Net-(IC3D-+IN)") (class "Default")
      (node (ref "IC3") (pin "12") (pinfunction "+IN_12") (pintype "input"))
      (node (ref "IC4") (pin "8") (pinfunction "VOUTC_8") (pintype "bidirectional"))
    )
    (net (code "42") (name "Net-(IC3D--IN)") (class "Default")
      (node (ref "C4") (pin "1") (pinfunction "1_1") (pintype "passive"))
      (node (ref "IC3") (pin "13") (pinfunction "-IN_13") (pintype "input"))
      (node (ref "R6") (pin "1") (pinfunction "1_1") (pintype "passive"))
      (node (ref "R7") (pin "2") (pinfunction "2_2") (pintype "passive"))
    )
    (net (code "43") (name "Net-(IC3D-OUT)") (class "Default")
      (node (ref "C4") (pin "2") (pinfunction "2_2") (pintype "passive"))
      (node (ref "IC3") (pin "14") (pinfunction "OUT_14") (pintype "output"))
      (node (ref "R10") (pin "1") (pinfunction "1_1") (pintype "passive"))
    )
    (net (code "44") (name "Net-(IC5A-AI)") (class "Default")
      (node (ref "CKOUT") (pin "1") (pinfunction "1_1") (pintype "passive"))
      (node (ref "IC5") (pin "3") (pinfunction "AI_3") (pintype "input"))
    )
    (net (code "45") (name "Net-(IC5A-AO)") (class "Default")
      (node (ref "IC5") (pin "2") (pinfunction "AO_2") (pintype "output"))
      (node (ref "R18") (pin "1") (pinfunction "1_1") (pintype "passive"))
    )
    (net (code "46") (name "Net-(IC5A-BI)") (class "Default")
      (node (ref "G2") (pin "1") (pinfunction "1_1") (pintype "passive"))
      (node (ref "IC5") (pin "5") (pinfunction "BI_5") (pintype "input"))
    )
    (net (code "47") (name "Net-(IC5A-BO)") (class "Default")
      (node (ref "IC5") (pin "4") (pinfunction "BO_4") (pintype "output"))
      (node (ref "R19") (pin "1") (pinfunction "1_1") (pintype "passive"))
    )
    (net (code "48") (name "Net-(IC5A-CI)") (class "Default")
      (node (ref "G1") (pin "1") (pinfunction "1_1") (pintype "passive"))
      (node (ref "IC5") (pin "7") (pinfunction "CI_7") (pintype "input"))
    )
    (net (code "49") (name "Net-(IC5A-CO)") (class "Default")
      (node (ref "IC5") (pin "6") (pinfunction "CO_6") (pintype "output"))
      (node (ref "R20") (pin "1") (pinfunction "1_1") (pintype "passive"))
    )
    (net (code "50") (name "Net-(IC5A-DI)") (class "Default")
      (node (ref "GX") (pin "1") (pinfunction "1_1") (pintype "passive"))
      (node (ref "IC5") (pin "9") (pinfunction "DI_9") (pintype "input"))
    )
    (net (code "51") (name "Net-(IC5A-DO)") (class "Default")
      (node (ref "IC5") (pin "10") (pinfunction "DO_10") (pintype "output"))
      (node (ref "R23") (pin "1") (pinfunction "1_1") (pintype "passive"))
    )
    (net (code "52") (name "Net-(IC5A-EI)") (class "Default")
      (node (ref "G4") (pin "1") (pinfunction "1_1") (pintype "passive"))
      (node (ref "IC5") (pin "11") (pinfunction "EI_11") (pintype "input"))
    )
    (net (code "53") (name "Net-(IC5A-EO)") (class "Default")
      (node (ref "IC5") (pin "12") (pinfunction "EO_12") (pintype "output"))
      (node (ref "R22") (pin "1") (pinfunction "1_1") (pintype "passive"))
    )
    (net (code "54") (name "Net-(IC5A-FI)") (class "Default")
      (node (ref "G3") (pin "1") (pinfunction "1_1") (pintype "passive"))
      (node (ref "IC5") (pin "14") (pinfunction "FI_14") (pintype "input"))
    )
    (net (code "55") (name "Net-(IC5A-FO)") (class "Default")
      (node (ref "IC5") (pin "15") (pinfunction "FO_15") (pintype "output"))
      (node (ref "R21") (pin "1") (pinfunction "1_1") (pintype "passive"))
    )
    (net (code "56") (name "Net-(IC6A-O)") (class "Default")
      (node (ref "CLKIN") (pin "1") (pinfunction "1_1") (pintype "passive"))
      (node (ref "IC6") (pin "4") (pinfunction "O_4") (pintype "output"))
    )
    (net (code "57") (name "Net-(IC7-G1)") (class "Default")
      (node (ref "IC7") (pin "2") (pinfunction "G1_2") (pintype "bidirectional"))
      (node (ref "R26") (pin "2") (pinfunction "2_2") (pintype "passive"))
      (node (ref "R27") (pin "2") (pinfunction "2_2") (pintype "passive"))
    )
    (net (code "58") (name "Net-(IC7-G2)") (class "Default")
      (node (ref "IC7") (pin "4") (pinfunction "G2_4") (pintype "bidirectional"))
      (node (ref "IC7") (pin "7") (pinfunction "D1_7") (pintype "bidirectional"))
      (node (ref "IC7") (pin "8") (pinfunction "D1_8") (pintype "bidirectional"))
      (node (ref "ON") (pin "2") (pinfunction "S1_2") (pintype "passive"))
      (node (ref "R25") (pin "2") (pinfunction "2_2") (pintype "passive"))
    )
    (net (code "59") (name "Net-(IC8-COMP)") (class "Default")
      (node (ref "IC8") (pin "5") (pinfunction "COMP_5") (pintype "bidirectional"))
      (node (ref "R30") (pin "2") (pinfunction "2_2") (pintype "passive"))
      (node (ref "R31") (pin "2") (pinfunction "2_2") (pintype "passive"))
    )
    (net (code "60") (name "Net-(IC8-DR_C)") (class "Default")
      (node (ref "IC8") (pin "1") (pinfunction "SW_C_1") (pintype "bidirectional"))
      (node (ref "IC8") (pin "7") (pinfunction "SENS_7") (pintype "bidirectional"))
      (node (ref "IC8") (pin "8") (pinfunction "DR_C_8") (pintype "bidirectional"))
      (node (ref "R29") (pin "2") (pinfunction "2_2") (pintype "passive"))
    )
    (net (code "61") (name "Net-(IC8-SW_E)") (class "Default")
      (node (ref "D5") (pin "C") (pinfunction "C_C") (pintype "passive"))
      (node (ref "IC8") (pin "2") (pinfunction "SW_E_2") (pintype "bidirectional"))
      (node (ref "L2") (pin "2") (pinfunction "2_2") (pintype "passive"))
    )
    (net (code "62") (name "Net-(IC8-TC)") (class "Default")
      (node (ref "C15") (pin "1") (pinfunction "1_1") (pintype "passive"))
      (node (ref "IC8") (pin "3") (pinfunction "TC_3") (pintype "bidirectional"))
    )
    (net (code "63") (name "Net-(MIDI_IN-Pad5)") (class "Default")
      (node (ref "MIDI_IN") (pin "5") (pinfunction "5_5") (pintype "passive"))
      (node (ref "R1") (pin "1") (pinfunction "1_1") (pintype "passive"))
    )
    (net (code "64") (name "Net-(MIDI_OUT-Pad4)") (class "Default")
      (node (ref "MIDI_OUT") (pin "4") (pinfunction "4_4") (pintype "passive"))
      (node (ref "R5") (pin "1") (pinfunction "1_1") (pintype "passive"))
    )
    (net (code "65") (name "Net-(MIDI_OUT-Pad5)") (class "Default")
      (node (ref "MIDI_OUT") (pin "5") (pinfunction "5_5") (pintype "passive"))
      (node (ref "R3") (pin "1") (pinfunction "1_1") (pintype "passive"))
    )
    (net (code "66") (name "Net-(PWR-PadA)") (class "Default")
      (node (ref "PWR") (pin "A") (pinfunction "A_A") (pintype "passive"))
      (node (ref "R28") (pin "2") (pinfunction "2_2") (pintype "passive"))
    )
    (net (code "67") (name "Net-(PWRCTL-Pad1)") (class "Default")
      (node (ref "PWRCTL") (pin "1") (pinfunction "1_1") (pintype "passive"))
      (node (ref "R27") (pin "1") (pinfunction "1_1") (pintype "passive"))
    )
    (net (code "68") (name "unconnected-(CKIN-Pad3)") (class "Default")
      (node (ref "CKIN") (pin "3") (pinfunction "3_3") (pintype "bidirectional"))
    )
    (net (code "69") (name "unconnected-(CKO-Pad3)") (class "Default")
      (node (ref "CKO") (pin "3") (pinfunction "3_3") (pintype "bidirectional"))
    )
    (net (code "70") (name "unconnected-(CVA-Pad3)") (class "Default")
      (node (ref "CVA") (pin "3") (pinfunction "3_3") (pintype "bidirectional"))
    )
    (net (code "71") (name "unconnected-(CVB-Pad3)") (class "Default")
      (node (ref "CVB") (pin "3") (pinfunction "3_3") (pintype "bidirectional"))
    )
    (net (code "72") (name "unconnected-(CVC-Pad3)") (class "Default")
      (node (ref "CVC") (pin "3") (pinfunction "3_3") (pintype "bidirectional"))
    )
    (net (code "73") (name "unconnected-(CVD-Pad3)") (class "Default")
      (node (ref "CVD") (pin "3") (pinfunction "3_3") (pintype "bidirectional"))
    )
    (net (code "74") (name "unconnected-(GT1-Pad3)") (class "Default")
      (node (ref "GT1") (pin "3") (pinfunction "3_3") (pintype "bidirectional"))
    )
    (net (code "75") (name "unconnected-(GT2-Pad3)") (class "Default")
      (node (ref "GT2") (pin "3") (pinfunction "3_3") (pintype "bidirectional"))
    )
    (net (code "76") (name "unconnected-(GT3-Pad3)") (class "Default")
      (node (ref "GT3") (pin "3") (pinfunction "3_3") (pintype "bidirectional"))
    )
    (net (code "77") (name "unconnected-(GT4-Pad3)") (class "Default")
      (node (ref "GT4") (pin "3") (pinfunction "3_3") (pintype "bidirectional"))
    )
    (net (code "78") (name "unconnected-(IC4-READY-Pad5)") (class "Default")
      (node (ref "IC4") (pin "5") (pinfunction "READY_5") (pintype "bidirectional"))
    )
    (net (code "79") (name "unconnected-(MIDI_IN-Pad1)") (class "Default")
      (node (ref "MIDI_IN") (pin "1") (pinfunction "1_1") (pintype "passive"))
    )
    (net (code "80") (name "unconnected-(MIDI_IN-Pad2)") (class "Default")
      (node (ref "MIDI_IN") (pin "2") (pinfunction "2_2") (pintype "passive"))
    )
    (net (code "81") (name "unconnected-(MIDI_IN-Pad3)") (class "Default")
      (node (ref "MIDI_IN") (pin "3") (pinfunction "3_3") (pintype "passive"))
    )
    (net (code "82") (name "unconnected-(MIDI_OUT-Pad1)") (class "Default")
      (node (ref "MIDI_OUT") (pin "1") (pinfunction "1_1") (pintype "passive"))
    )
    (net (code "83") (name "unconnected-(MIDI_OUT-Pad3)") (class "Default")
      (node (ref "MIDI_OUT") (pin "3") (pinfunction "3_3") (pintype "passive"))
    )
    (net (code "84") (name "unconnected-(OFF-P1-Pad4)") (class "Default")
      (node (ref "OFF") (pin "4") (pinfunction "P1_4") (pintype "passive"))
    )
    (net (code "85") (name "unconnected-(OFF-S-Pad1)") (class "Default")
      (node (ref "OFF") (pin "1") (pinfunction "S_1") (pintype "passive"))
    )
    (net (code "86") (name "unconnected-(ON-P1-Pad4)") (class "Default")
      (node (ref "ON") (pin "4") (pinfunction "P1_4") (pintype "passive"))
    )
    (net (code "87") (name "unconnected-(ON-S-Pad1)") (class "Default")
      (node (ref "ON") (pin "1") (pinfunction "S_1") (pintype "passive"))
    )
  )
)
